# PH-Meter.net
KiCad netlist of a schematic drawn in EAGLE
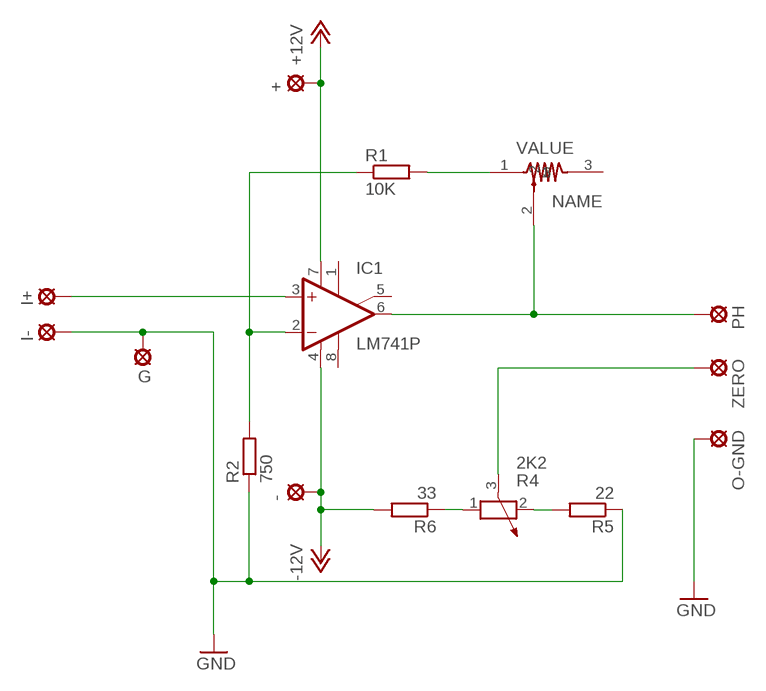
[diagram p0: schematic, sheet 1]

(export (version "E")
  (design (tool "Eeschema 10.0.6"))
  (components
    (comp (ref "+")
      (value "LSP10")
      (footprint "eagle-import:LSP10")
      (libsource (lib "eagle-import") (part "LSP10"))
    )
    (comp (ref "-")
      (value "LSP10")
      (footprint "eagle-import:LSP10")
      (libsource (lib "eagle-import") (part "LSP10"))
    )
    (comp (ref "G")
      (value "LSP10")
      (footprint "eagle-import:LSP10")
      (libsource (lib "eagle-import") (part "LSP10"))
    )
    (comp (ref "I+")
      (value "LSP10")
      (footprint "eagle-import:LSP10")
      (libsource (lib "eagle-import") (part "LSP10"))
    )
    (comp (ref "I-")
      (value "LSP10")
      (footprint "eagle-import:LSP10")
      (libsource (lib "eagle-import") (part "LSP10"))
    )
    (comp (ref "IC1")
      (value "LM741P")
      (footprint "eagle-import:DIL08")
      (libsource (lib "eagle-import") (part "741PLM"))
    )
    (comp (ref "O-GND")
      (value "LSP10")
      (footprint "eagle-import:LSP10")
      (libsource (lib "eagle-import") (part "LSP10"))
    )
    (comp (ref "PH")
      (value "LSP10")
      (footprint "eagle-import:LSP10")
      (libsource (lib "eagle-import") (part "LSP10"))
    )
    (comp (ref "R1")
      (value "10K")
      (footprint "eagle-import:0207_12")
      (libsource (lib "eagle-import") (part "R-EU_0207/12"))
    )
    (comp (ref "R2")
      (value "750")
      (footprint "eagle-import:0207_12")
      (libsource (lib "eagle-import") (part "R-EU_0207/12"))
    )
    (comp (ref "R3")
      (value "2K")
      (footprint "eagle-import:TRIMMER")
      (libsource (lib "eagle-import") (part "TRIMMER"))
    )
    (comp (ref "R4")
      (value "2K2")
      (footprint "eagle-import:PT-10")
      (libsource (lib "eagle-import") (part "POTENTIOMETER_PT-10"))
    )
    (comp (ref "R5")
      (value "22")
      (footprint "eagle-import:0207_12")
      (libsource (lib "eagle-import") (part "R-EU_0207/12"))
    )
    (comp (ref "R6")
      (value "33")
      (footprint "eagle-import:0207_12")
      (libsource (lib "eagle-import") (part "R-EU_0207/12"))
    )
    (comp (ref "ZERO")
      (value "LSP10")
      (footprint "eagle-import:LSP10")
      (libsource (lib "eagle-import") (part "LSP10"))
    )
  )
  (nets
    (net (code "1") (name "+12V") (class "Default")
      (node (ref "+") (pin "MP") (pinfunction "MP_MP") (pintype "passive"))
      (node (ref "IC1") (pin "7") (pinfunction "V+_7") (pintype "power_in"))
    )
    (net (code "2") (name "-12V") (class "Default")
      (node (ref "-") (pin "MP") (pinfunction "MP_MP") (pintype "passive"))
      (node (ref "IC1") (pin "4") (pinfunction "V-_4") (pintype "power_in"))
      (node (ref "R6") (pin "2") (pinfunction "2_2") (pintype "passive"))
    )
    (net (code "3") (name "GND") (class "Default")
      (node (ref "G") (pin "MP") (pinfunction "MP_MP") (pintype "passive"))
      (node (ref "I-") (pin "MP") (pinfunction "MP_MP") (pintype "passive"))
      (node (ref "O-GND") (pin "MP") (pinfunction "MP_MP") (pintype "passive"))
      (node (ref "R2") (pin "1") (pinfunction "1_1") (pintype "passive"))
      (node (ref "R5") (pin "1") (pinfunction "1_1") (pintype "passive"))
    )
    (net (code "4") (name "Net-(IC1-+IN)") (class "Default")
      (node (ref "I+") (pin "MP") (pinfunction "MP_MP") (pintype "passive"))
      (node (ref "IC1") (pin "3") (pinfunction "+IN_3") (pintype "input"))
    )
    (net (code "5") (name "Net-(IC1--IN)") (class "Default")
      (node (ref "IC1") (pin "2") (pinfunction "-IN_2") (pintype "input"))
      (node (ref "R1") (pin "1") (pinfunction "1_1") (pintype "passive"))
      (node (ref "R2") (pin "2") (pinfunction "2_2") (pintype "passive"))
    )
    (net (code "6") (name "Net-(IC1-OUT)") (class "Default")
      (node (ref "IC1") (pin "6") (pinfunction "OUT_6") (pintype "output"))
      (node (ref "PH") (pin "MP") (pinfunction "MP_MP") (pintype "passive"))
      (node (ref "R3") (pin "2") (pinfunction "2_2") (pintype "bidirectional"))
    )
    (net (code "7") (name "Net-(R1-Pad2)") (class "Default")
      (node (ref "R1") (pin "2") (pinfunction "2_2") (pintype "passive"))
      (node (ref "R3") (pin "1") (pinfunction "1_1") (pintype "bidirectional"))
    )
    (net (code "8") (name "Net-(R4-Pad1)") (class "Default")
      (node (ref "R4") (pin "1") (pinfunction "1_1") (pintype "passive"))
      (node (ref "R6") (pin "1") (pinfunction "1_1") (pintype "passive"))
    )
    (net (code "9") (name "Net-(R4-Pad2)") (class "Default")
      (node (ref "R4") (pin "2") (pinfunction "2_2") (pintype "passive"))
      (node (ref "R5") (pin "2") (pinfunction "2_2") (pintype "passive"))
    )
    (net (code "10") (name "Net-(R4-Pad3)") (class "Default")
      (node (ref "R4") (pin "3") (pinfunction "3_3") (pintype "passive"))
      (node (ref "ZERO") (pin "MP") (pinfunction "MP_MP") (pintype "passive"))
    )
    (net (code "11") (name "unconnected-(IC1-ON1-Pad1)") (class "Default")
      (node (ref "IC1") (pin "1") (pinfunction "ON1_1") (pintype "passive"))
    )
    (net (code "12") (name "unconnected-(IC1-ON2-Pad5)") (class "Default")
      (node (ref "IC1") (pin "5") (pinfunction "ON2_5") (pintype "passive"))
    )
    (net (code "13") (name "unconnected-(IC1-OPT-Pad8)") (class "Default")
      (node (ref "IC1") (pin "8") (pinfunction "OPT_8") (pintype "passive"))
    )
    (net (code "14") (name "unconnected-(R3-Pad3)") (class "Default")
      (node (ref "R3") (pin "3") (pinfunction "3_3") (pintype "bidirectional"))
    )
  )
)
